# RTDsSheet1.net
KiCad netlist of a schematic drawn in Altium Designer
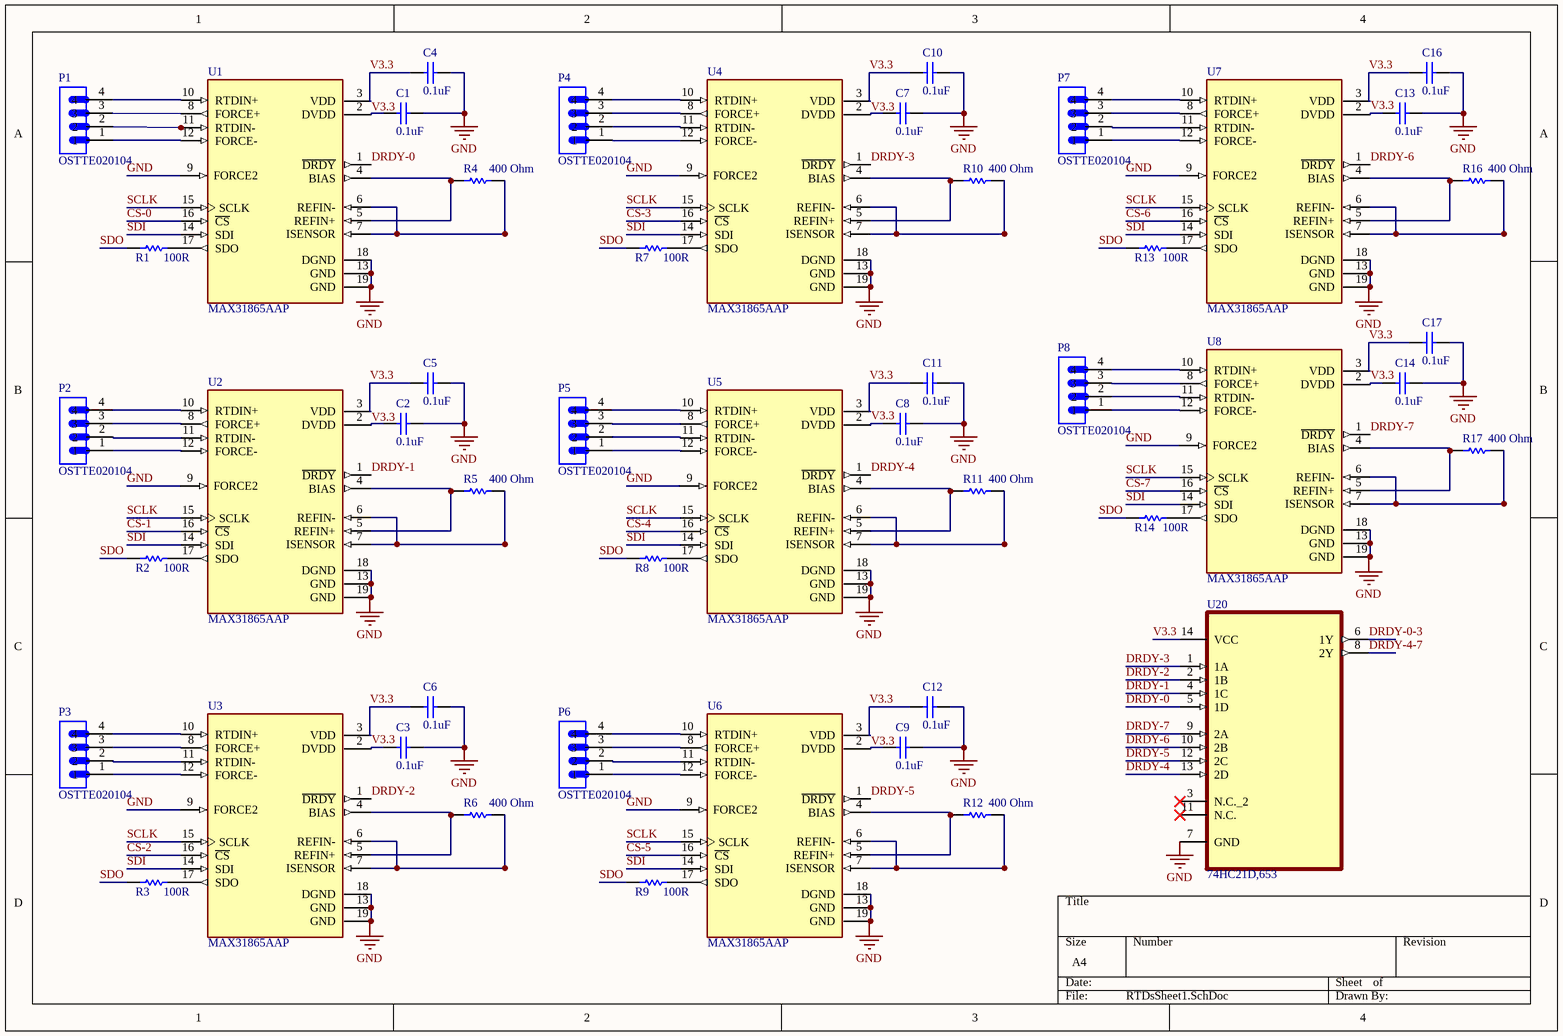
[diagram p0: RTDsSheet1.SchDoc]

(export (version "E")
  (design (tool "Eeschema 10.0.6"))
  (components
    (comp (ref "C1")
      (value "0.1uF")
      (footprint "1608[0603]")
      (description "Capacitor (Semiconductor SIM Model)")
      (fields (field (name "PUBLISHER") "Altium Limited"))
      (libsource (lib "Miscellaneous Devices") (part "Cap Semi"))
    )
    (comp (ref "C2")
      (value "0.1uF")
      (footprint "1608[0603]")
      (description "Capacitor (Semiconductor SIM Model)")
      (fields (field (name "PUBLISHER") "Altium Limited"))
      (libsource (lib "Miscellaneous Devices") (part "Cap Semi"))
    )
    (comp (ref "C3")
      (value "0.1uF")
      (footprint "1608[0603]")
      (description "Capacitor (Semiconductor SIM Model)")
      (fields (field (name "PUBLISHER") "Altium Limited"))
      (libsource (lib "Miscellaneous Devices") (part "Cap Semi"))
    )
    (comp (ref "C4")
      (value "0.1uF")
      (footprint "1608[0603]")
      (description "Capacitor (Semiconductor SIM Model)")
      (fields (field (name "PUBLISHER") "Altium Limited"))
      (libsource (lib "Miscellaneous Devices") (part "Cap Semi"))
    )
    (comp (ref "C5")
      (value "0.1uF")
      (footprint "1608[0603]")
      (description "Capacitor (Semiconductor SIM Model)")
      (fields (field (name "PUBLISHER") "Altium Limited"))
      (libsource (lib "Miscellaneous Devices") (part "Cap Semi"))
    )
    (comp (ref "C6")
      (value "0.1uF")
      (footprint "1608[0603]")
      (description "Capacitor (Semiconductor SIM Model)")
      (fields (field (name "PUBLISHER") "Altium Limited"))
      (libsource (lib "Miscellaneous Devices") (part "Cap Semi"))
    )
    (comp (ref "C7")
      (value "0.1uF")
      (footprint "1608[0603]")
      (description "Capacitor (Semiconductor SIM Model)")
      (fields (field (name "PUBLISHER") "Altium Limited"))
      (libsource (lib "Miscellaneous Devices") (part "Cap Semi"))
    )
    (comp (ref "C8")
      (value "0.1uF")
      (footprint "1608[0603]")
      (description "Capacitor (Semiconductor SIM Model)")
      (fields (field (name "PUBLISHER") "Altium Limited"))
      (libsource (lib "Miscellaneous Devices") (part "Cap Semi"))
    )
    (comp (ref "C9")
      (value "0.1uF")
      (footprint "1608[0603]")
      (description "Capacitor (Semiconductor SIM Model)")
      (fields (field (name "PUBLISHER") "Altium Limited"))
      (libsource (lib "Miscellaneous Devices") (part "Cap Semi"))
    )
    (comp (ref "C10")
      (value "0.1uF")
      (footprint "1608[0603]")
      (description "Capacitor (Semiconductor SIM Model)")
      (fields (field (name "PUBLISHER") "Altium Limited"))
      (libsource (lib "Miscellaneous Devices") (part "Cap Semi"))
    )
    (comp (ref "C11")
      (value "0.1uF")
      (footprint "1608[0603]")
      (description "Capacitor (Semiconductor SIM Model)")
      (fields (field (name "PUBLISHER") "Altium Limited"))
      (libsource (lib "Miscellaneous Devices") (part "Cap Semi"))
    )
    (comp (ref "C12")
      (value "0.1uF")
      (footprint "1608[0603]")
      (description "Capacitor (Semiconductor SIM Model)")
      (fields (field (name "PUBLISHER") "Altium Limited"))
      (libsource (lib "Miscellaneous Devices") (part "Cap Semi"))
    )
    (comp (ref "C13")
      (value "0.1uF")
      (footprint "1608[0603]")
      (description "Capacitor (Semiconductor SIM Model)")
      (fields (field (name "PUBLISHER") "Altium Limited"))
      (libsource (lib "Miscellaneous Devices") (part "Cap Semi"))
    )
    (comp (ref "C14")
      (value "0.1uF")
      (footprint "1608[0603]")
      (description "Capacitor (Semiconductor SIM Model)")
      (fields (field (name "PUBLISHER") "Altium Limited"))
      (libsource (lib "Miscellaneous Devices") (part "Cap Semi"))
    )
    (comp (ref "C16")
      (value "0.1uF")
      (footprint "1608[0603]")
      (description "Capacitor (Semiconductor SIM Model)")
      (fields (field (name "PUBLISHER") "Altium Limited"))
      (libsource (lib "Miscellaneous Devices") (part "Cap Semi"))
    )
    (comp (ref "C17")
      (value "0.1uF")
      (footprint "1608[0603]")
      (description "Capacitor (Semiconductor SIM Model)")
      (fields (field (name "PUBLISHER") "Altium Limited"))
      (libsource (lib "Miscellaneous Devices") (part "Cap Semi"))
    )
    (comp (ref "P1")
      (value "OSTTE020104")
      (footprint "3-641209-4:TE_3-641209-4")
      (description "Terminal Block 3.5mm 2pos Pcb")
      (fields (field (name "MF") "{'manufacturer': u'On Shore'}"))
      (libsource (lib "OSTTE040104") (part "OSTTE020104"))
    )
    (comp (ref "P2")
      (value "OSTTE020104")
      (footprint "3-641209-4:TE_3-641209-4")
      (description "Terminal Block 3.5mm 2pos Pcb")
      (fields (field (name "MF") "{'manufacturer': u'On Shore'}"))
      (libsource (lib "OSTTE040104") (part "OSTTE020104"))
    )
    (comp (ref "P3")
      (value "OSTTE020104")
      (footprint "3-641209-4:TE_3-641209-4")
      (description "Terminal Block 3.5mm 2pos Pcb")
      (fields (field (name "MF") "{'manufacturer': u'On Shore'}"))
      (libsource (lib "OSTTE040104") (part "OSTTE020104"))
    )
    (comp (ref "P4")
      (value "OSTTE020104")
      (footprint "3-641209-4:TE_3-641209-4")
      (description "Terminal Block 3.5mm 2pos Pcb")
      (fields (field (name "MF") "{'manufacturer': u'On Shore'}"))
      (libsource (lib "OSTTE040104") (part "OSTTE020104"))
    )
    (comp (ref "P5")
      (value "OSTTE020104")
      (footprint "3-641209-4:TE_3-641209-4")
      (description "Terminal Block 3.5mm 2pos Pcb")
      (fields (field (name "MF") "{'manufacturer': u'On Shore'}"))
      (libsource (lib "OSTTE040104") (part "OSTTE020104"))
    )
    (comp (ref "P6")
      (value "OSTTE020104")
      (footprint "3-641209-4:TE_3-641209-4")
      (description "Terminal Block 3.5mm 2pos Pcb")
      (fields (field (name "MF") "{'manufacturer': u'On Shore'}"))
      (libsource (lib "OSTTE040104") (part "OSTTE020104"))
    )
    (comp (ref "P7")
      (value "OSTTE020104")
      (footprint "3-641209-4:TE_3-641209-4")
      (description "Terminal Block 3.5mm 2pos Pcb")
      (fields (field (name "MF") "{'manufacturer': u'On Shore'}"))
      (libsource (lib "OSTTE040104") (part "OSTTE020104"))
    )
    (comp (ref "P8")
      (value "OSTTE020104")
      (footprint "3-641209-4:TE_3-641209-4")
      (description "Terminal Block 3.5mm 2pos Pcb")
      (fields (field (name "MF") "{'manufacturer': u'On Shore'}"))
      (libsource (lib "OSTTE040104") (part "OSTTE020104"))
    )
    (comp (ref "R1")
      (value "100R")
      (footprint "1608[0603]")
      (description "Semiconductor Resistor")
      (fields (field (name "PUBLISHER") "Altium Limited"))
      (libsource (lib "Miscellaneous Devices") (part "Res Semi"))
    )
    (comp (ref "R2")
      (value "100R")
      (footprint "1608[0603]")
      (description "Semiconductor Resistor")
      (fields (field (name "PUBLISHER") "Altium Limited"))
      (libsource (lib "Miscellaneous Devices") (part "Res Semi"))
    )
    (comp (ref "R3")
      (value "100R")
      (footprint "1608[0603]")
      (description "Semiconductor Resistor")
      (fields (field (name "PUBLISHER") "Altium Limited"))
      (libsource (lib "Miscellaneous Devices") (part "Res Semi"))
    )
    (comp (ref "R4")
      (value "400 Ohm")
      (footprint "6-0805_M")
      (description "Semiconductor Resistor")
      (fields (field (name "PUBLISHER") "Altium Limited"))
      (libsource (lib "Miscellaneous Devices") (part "Res Semi"))
    )
    (comp (ref "R5")
      (value "400 Ohm")
      (footprint "6-0805_M")
      (description "Semiconductor Resistor")
      (fields (field (name "PUBLISHER") "Altium Limited"))
      (libsource (lib "Miscellaneous Devices") (part "Res Semi"))
    )
    (comp (ref "R6")
      (value "400 Ohm")
      (footprint "6-0805_M")
      (description "Semiconductor Resistor")
      (fields (field (name "PUBLISHER") "Altium Limited"))
      (libsource (lib "Miscellaneous Devices") (part "Res Semi"))
    )
    (comp (ref "R7")
      (value "100R")
      (footprint "1608[0603]")
      (description "Semiconductor Resistor")
      (fields (field (name "PUBLISHER") "Altium Limited"))
      (libsource (lib "Miscellaneous Devices") (part "Res Semi"))
    )
    (comp (ref "R8")
      (value "100R")
      (footprint "1608[0603]")
      (description "Semiconductor Resistor")
      (fields (field (name "PUBLISHER") "Altium Limited"))
      (libsource (lib "Miscellaneous Devices") (part "Res Semi"))
    )
    (comp (ref "R9")
      (value "100R")
      (footprint "1608[0603]")
      (description "Semiconductor Resistor")
      (fields (field (name "PUBLISHER") "Altium Limited"))
      (libsource (lib "Miscellaneous Devices") (part "Res Semi"))
    )
    (comp (ref "R10")
      (value "400 Ohm")
      (footprint "6-0805_M")
      (description "Semiconductor Resistor")
      (fields (field (name "PUBLISHER") "Altium Limited"))
      (libsource (lib "Miscellaneous Devices") (part "Res Semi"))
    )
    (comp (ref "R11")
      (value "400 Ohm")
      (footprint "6-0805_M")
      (description "Semiconductor Resistor")
      (fields (field (name "PUBLISHER") "Altium Limited"))
      (libsource (lib "Miscellaneous Devices") (part "Res Semi"))
    )
    (comp (ref "R12")
      (value "400 Ohm")
      (footprint "6-0805_M")
      (description "Semiconductor Resistor")
      (fields (field (name "PUBLISHER") "Altium Limited"))
      (libsource (lib "Miscellaneous Devices") (part "Res Semi"))
    )
    (comp (ref "R13")
      (value "100R")
      (footprint "1608[0603]")
      (description "Semiconductor Resistor")
      (fields (field (name "PUBLISHER") "Altium Limited"))
      (libsource (lib "Miscellaneous Devices") (part "Res Semi"))
    )
    (comp (ref "R14")
      (value "100R")
      (footprint "1608[0603]")
      (description "Semiconductor Resistor")
      (fields (field (name "PUBLISHER") "Altium Limited"))
      (libsource (lib "Miscellaneous Devices") (part "Res Semi"))
    )
    (comp (ref "R16")
      (value "400 Ohm")
      (footprint "6-0805_M")
      (description "Semiconductor Resistor")
      (fields (field (name "PUBLISHER") "Altium Limited"))
      (libsource (lib "Miscellaneous Devices") (part "Res Semi"))
    )
    (comp (ref "R17")
      (value "400 Ohm")
      (footprint "6-0805_M")
      (description "Semiconductor Resistor")
      (fields (field (name "PUBLISHER") "Altium Limited"))
      (libsource (lib "Miscellaneous Devices") (part "Res Semi"))
    )
    (comp (ref "U1")
      (value "MAX31865AAP")
      (footprint "MAX31865AAP+:SOP65P777X199-20N")
      (description "Rtd To Digital Converter In Ssop Tr")
      (fields (field (name "MF") "{'manufacturer': u'Maxim Integrated'}"))
      (libsource (lib "MAX31865AAP+") (part "MAX31865AAP"))
    )
    (comp (ref "U2")
      (value "MAX31865AAP")
      (footprint "MAX31865AAP+:SOP65P777X199-20N")
      (description "Rtd To Digital Converter In Ssop Tr")
      (fields (field (name "MF") "{'manufacturer': u'Maxim Integrated'}"))
      (libsource (lib "MAX31865AAP+") (part "MAX31865AAP"))
    )
    (comp (ref "U3")
      (value "MAX31865AAP")
      (footprint "MAX31865AAP+:SOP65P777X199-20N")
      (description "Rtd To Digital Converter In Ssop Tr")
      (fields (field (name "MF") "{'manufacturer': u'Maxim Integrated'}"))
      (libsource (lib "MAX31865AAP+") (part "MAX31865AAP"))
    )
    (comp (ref "U4")
      (value "MAX31865AAP")
      (footprint "MAX31865AAP+:SOP65P777X199-20N")
      (description "Rtd To Digital Converter In Ssop Tr")
      (fields (field (name "MF") "{'manufacturer': u'Maxim Integrated'}"))
      (libsource (lib "MAX31865AAP+") (part "MAX31865AAP"))
    )
    (comp (ref "U5")
      (value "MAX31865AAP")
      (footprint "MAX31865AAP+:SOP65P777X199-20N")
      (description "Rtd To Digital Converter In Ssop Tr")
      (fields (field (name "MF") "{'manufacturer': u'Maxim Integrated'}"))
      (libsource (lib "MAX31865AAP+") (part "MAX31865AAP"))
    )
    (comp (ref "U6")
      (value "MAX31865AAP")
      (footprint "MAX31865AAP+:SOP65P777X199-20N")
      (description "Rtd To Digital Converter In Ssop Tr")
      (fields (field (name "MF") "{'manufacturer': u'Maxim Integrated'}"))
      (libsource (lib "MAX31865AAP+") (part "MAX31865AAP"))
    )
    (comp (ref "U7")
      (value "MAX31865AAP")
      (footprint "MAX31865AAP+:SOP65P777X199-20N")
      (description "Rtd To Digital Converter In Ssop Tr")
      (fields (field (name "MF") "{'manufacturer': u'Maxim Integrated'}"))
      (libsource (lib "MAX31865AAP+") (part "MAX31865AAP"))
    )
    (comp (ref "U8")
      (value "MAX31865AAP")
      (footprint "MAX31865AAP+:SOP65P777X199-20N")
      (description "Rtd To Digital Converter In Ssop Tr")
      (fields (field (name "MF") "{'manufacturer': u'Maxim Integrated'}"))
      (libsource (lib "MAX31865AAP+") (part "MAX31865AAP"))
    )
    (comp (ref "U20")
      (value "74HC21D,653")
      (footprint "74HC21D,653:SOIC127P600X175-14N")
      (description "Dual 4-input AND gate")
      (fields (field (name "MF") "{'manufacturer': u'Nexperia USA'}"))
      (libsource (lib "*") (part "74HC21D,653"))
    )
  )
  (nets
    (net (code "1") (name "/CS-0") (class "Default")
      (node (ref "U1") (pin "16") (pinfunction "~{CS}_16") (pintype "input"))
    )
    (net (code "2") (name "/CS-1") (class "Default")
      (node (ref "U2") (pin "16") (pinfunction "~{CS}_16") (pintype "input"))
    )
    (net (code "3") (name "/CS-2") (class "Default")
      (node (ref "U3") (pin "16") (pinfunction "~{CS}_16") (pintype "input"))
    )
    (net (code "4") (name "/CS-3") (class "Default")
      (node (ref "U4") (pin "16") (pinfunction "~{CS}_16") (pintype "input"))
    )
    (net (code "5") (name "/CS-4") (class "Default")
      (node (ref "U5") (pin "16") (pinfunction "~{CS}_16") (pintype "input"))
    )
    (net (code "6") (name "/CS-5") (class "Default")
      (node (ref "U6") (pin "16") (pinfunction "~{CS}_16") (pintype "input"))
    )
    (net (code "7") (name "/CS-6") (class "Default")
      (node (ref "U7") (pin "16") (pinfunction "~{CS}_16") (pintype "input"))
    )
    (net (code "8") (name "/CS-7") (class "Default")
      (node (ref "U8") (pin "16") (pinfunction "~{CS}_16") (pintype "input"))
    )
    (net (code "9") (name "/DRDY-0") (class "Default")
      (node (ref "U1") (pin "1") (pinfunction "~{DRDY}_1") (pintype "output"))
      (node (ref "U20") (pin "5") (pinfunction "1D_5") (pintype "input"))
    )
    (net (code "10") (name "/DRDY-0-3") (class "Default")
      (node (ref "U20") (pin "6") (pinfunction "1Y_6") (pintype "output"))
    )
    (net (code "11") (name "/DRDY-1") (class "Default")
      (node (ref "U2") (pin "1") (pinfunction "~{DRDY}_1") (pintype "output"))
      (node (ref "U20") (pin "4") (pinfunction "1C_4") (pintype "input"))
    )
    (net (code "12") (name "/DRDY-2") (class "Default")
      (node (ref "U20") (pin "2") (pinfunction "1B_2") (pintype "input"))
      (node (ref "U3") (pin "1") (pinfunction "~{DRDY}_1") (pintype "output"))
    )
    (net (code "13") (name "/DRDY-3") (class "Default")
      (node (ref "U20") (pin "1") (pinfunction "1A_1") (pintype "input"))
      (node (ref "U4") (pin "1") (pinfunction "~{DRDY}_1") (pintype "output"))
    )
    (net (code "14") (name "/DRDY-4") (class "Default")
      (node (ref "U20") (pin "13") (pinfunction "2D_13") (pintype "input"))
      (node (ref "U5") (pin "1") (pinfunction "~{DRDY}_1") (pintype "output"))
    )
    (net (code "15") (name "/DRDY-4-7") (class "Default")
      (node (ref "U20") (pin "8") (pinfunction "2Y_8") (pintype "output"))
    )
    (net (code "16") (name "/DRDY-5") (class "Default")
      (node (ref "U20") (pin "12") (pinfunction "2C_12") (pintype "input"))
      (node (ref "U6") (pin "1") (pinfunction "~{DRDY}_1") (pintype "output"))
    )
    (net (code "17") (name "/DRDY-6") (class "Default")
      (node (ref "U20") (pin "10") (pinfunction "2B_10") (pintype "input"))
      (node (ref "U7") (pin "1") (pinfunction "~{DRDY}_1") (pintype "output"))
    )
    (net (code "18") (name "/DRDY-7") (class "Default")
      (node (ref "U20") (pin "9") (pinfunction "2A_9") (pintype "input"))
      (node (ref "U8") (pin "1") (pinfunction "~{DRDY}_1") (pintype "output"))
    )
    (net (code "19") (name "/SCLK") (class "Default")
      (node (ref "U1") (pin "15") (pinfunction "SCLK_15") (pintype "input"))
      (node (ref "U2") (pin "15") (pinfunction "SCLK_15") (pintype "input"))
      (node (ref "U3") (pin "15") (pinfunction "SCLK_15") (pintype "input"))
      (node (ref "U4") (pin "15") (pinfunction "SCLK_15") (pintype "input"))
      (node (ref "U5") (pin "15") (pinfunction "SCLK_15") (pintype "input"))
      (node (ref "U6") (pin "15") (pinfunction "SCLK_15") (pintype "input"))
      (node (ref "U7") (pin "15") (pinfunction "SCLK_15") (pintype "input"))
      (node (ref "U8") (pin "15") (pinfunction "SCLK_15") (pintype "input"))
    )
    (net (code "20") (name "/SDI") (class "Default")
      (node (ref "U1") (pin "14") (pinfunction "SDI_14") (pintype "input"))
      (node (ref "U2") (pin "14") (pinfunction "SDI_14") (pintype "input"))
      (node (ref "U3") (pin "14") (pinfunction "SDI_14") (pintype "input"))
      (node (ref "U4") (pin "14") (pinfunction "SDI_14") (pintype "input"))
      (node (ref "U5") (pin "14") (pinfunction "SDI_14") (pintype "input"))
      (node (ref "U6") (pin "14") (pinfunction "SDI_14") (pintype "input"))
      (node (ref "U7") (pin "14") (pinfunction "SDI_14") (pintype "input"))
      (node (ref "U8") (pin "14") (pinfunction "SDI_14") (pintype "input"))
    )
    (net (code "21") (name "/SDO") (class "Default")
      (node (ref "R1") (pin "2") (pinfunction "2_2") (pintype "passive"))
      (node (ref "R13") (pin "2") (pinfunction "2_2") (pintype "passive"))
      (node (ref "R14") (pin "2") (pinfunction "2_2") (pintype "passive"))
      (node (ref "R2") (pin "2") (pinfunction "2_2") (pintype "passive"))
      (node (ref "R3") (pin "2") (pinfunction "2_2") (pintype "passive"))
      (node (ref "R7") (pin "2") (pinfunction "2_2") (pintype "passive"))
      (node (ref "R8") (pin "2") (pinfunction "2_2") (pintype "passive"))
      (node (ref "R9") (pin "2") (pinfunction "2_2") (pintype "passive"))
    )
    (net (code "22") (name "/V3.3") (class "Default")
      (node (ref "C1") (pin "2") (pinfunction "2_2") (pintype "passive"))
      (node (ref "C10") (pin "2") (pinfunction "2_2") (pintype "passive"))
      (node (ref "C11") (pin "2") (pinfunction "2_2") (pintype "passive"))
      (node (ref "C12") (pin "2") (pinfunction "2_2") (pintype "passive"))
      (node (ref "C13") (pin "2") (pinfunction "2_2") (pintype "passive"))
      (node (ref "C14") (pin "2") (pinfunction "2_2") (pintype "passive"))
      (node (ref "C16") (pin "2") (pinfunction "2_2") (pintype "passive"))
      (node (ref "C17") (pin "2") (pinfunction "2_2") (pintype "passive"))
      (node (ref "C2") (pin "2") (pinfunction "2_2") (pintype "passive"))
      (node (ref "C3") (pin "2") (pinfunction "2_2") (pintype "passive"))
      (node (ref "C4") (pin "2") (pinfunction "2_2") (pintype "passive"))
      (node (ref "C5") (pin "2") (pinfunction "2_2") (pintype "passive"))
      (node (ref "C6") (pin "2") (pinfunction "2_2") (pintype "passive"))
      (node (ref "C7") (pin "2") (pinfunction "2_2") (pintype "passive"))
      (node (ref "C8") (pin "2") (pinfunction "2_2") (pintype "passive"))
      (node (ref "C9") (pin "2") (pinfunction "2_2") (pintype "passive"))
      (node (ref "U1") (pin "2") (pinfunction "DVDD_2") (pintype "power_in"))
      (node (ref "U1") (pin "3") (pinfunction "VDD_3") (pintype "power_in"))
      (node (ref "U2") (pin "2") (pinfunction "DVDD_2") (pintype "power_in"))
      (node (ref "U2") (pin "3") (pinfunction "VDD_3") (pintype "power_in"))
      (node (ref "U20") (pin "14") (pinfunction "VCC_14") (pintype "power_in"))
      (node (ref "U3") (pin "2") (pinfunction "DVDD_2") (pintype "power_in"))
      (node (ref "U3") (pin "3") (pinfunction "VDD_3") (pintype "power_in"))
      (node (ref "U4") (pin "2") (pinfunction "DVDD_2") (pintype "power_in"))
      (node (ref "U4") (pin "3") (pinfunction "VDD_3") (pintype "power_in"))
      (node (ref "U5") (pin "2") (pinfunction "DVDD_2") (pintype "power_in"))
      (node (ref "U5") (pin "3") (pinfunction "VDD_3") (pintype "power_in"))
      (node (ref "U6") (pin "2") (pinfunction "DVDD_2") (pintype "power_in"))
      (node (ref "U6") (pin "3") (pinfunction "VDD_3") (pintype "power_in"))
      (node (ref "U7") (pin "2") (pinfunction "DVDD_2") (pintype "power_in"))
      (node (ref "U7") (pin "3") (pinfunction "VDD_3") (pintype "power_in"))
      (node (ref "U8") (pin "2") (pinfunction "DVDD_2") (pintype "power_in"))
      (node (ref "U8") (pin "3") (pinfunction "VDD_3") (pintype "power_in"))
    )
    (net (code "23") (name "GND") (class "Default")
      (node (ref "C1") (pin "1") (pinfunction "1_1") (pintype "passive"))
      (node (ref "C10") (pin "1") (pinfunction "1_1") (pintype "passive"))
      (node (ref "C11") (pin "1") (pinfunction "1_1") (pintype "passive"))
      (node (ref "C12") (pin "1") (pinfunction "1_1") (pintype "passive"))
      (node (ref "C13") (pin "1") (pinfunction "1_1") (pintype "passive"))
      (node (ref "C14") (pin "1") (pinfunction "1_1") (pintype "passive"))
      (node (ref "C16") (pin "1") (pinfunction "1_1") (pintype "passive"))
      (node (ref "C17") (pin "1") (pinfunction "1_1") (pintype "passive"))
      (node (ref "C2") (pin "1") (pinfunction "1_1") (pintype "passive"))
      (node (ref "C3") (pin "1") (pinfunction "1_1") (pintype "passive"))
      (node (ref "C4") (pin "1") (pinfunction "1_1") (pintype "passive"))
      (node (ref "C5") (pin "1") (pinfunction "1_1") (pintype "passive"))
      (node (ref "C6") (pin "1") (pinfunction "1_1") (pintype "passive"))
      (node (ref "C7") (pin "1") (pinfunction "1_1") (pintype "passive"))
      (node (ref "C8") (pin "1") (pinfunction "1_1") (pintype "passive"))
      (node (ref "C9") (pin "1") (pinfunction "1_1") (pintype "passive"))
      (node (ref "U1") (pin "13") (pinfunction "GND_13") (pintype "power_in"))
      (node (ref "U1") (pin "18") (pinfunction "DGND_18") (pintype "power_in"))
      (node (ref "U1") (pin "19") (pinfunction "GND_19") (pintype "power_in"))
      (node (ref "U1") (pin "9") (pinfunction "FORCE2_9") (pintype "input"))
      (node (ref "U2") (pin "13") (pinfunction "GND_13") (pintype "power_in"))
      (node (ref "U2") (pin "18") (pinfunction "DGND_18") (pintype "power_in"))
      (node (ref "U2") (pin "19") (pinfunction "GND_19") (pintype "power_in"))
      (node (ref "U2") (pin "9") (pinfunction "FORCE2_9") (pintype "input"))
      (node (ref "U20") (pin "7") (pinfunction "GND_7") (pintype "passive"))
      (node (ref "U3") (pin "13") (pinfunction "GND_13") (pintype "power_in"))
      (node (ref "U3") (pin "18") (pinfunction "DGND_18") (pintype "power_in"))
      (node (ref "U3") (pin "19") (pinfunction "GND_19") (pintype "power_in"))
      (node (ref "U3") (pin "9") (pinfunction "FORCE2_9") (pintype "input"))
      (node (ref "U4") (pin "13") (pinfunction "GND_13") (pintype "power_in"))
      (node (ref "U4") (pin "18") (pinfunction "DGND_18") (pintype "power_in"))
      (node (ref "U4") (pin "19") (pinfunction "GND_19") (pintype "power_in"))
      (node (ref "U4") (pin "9") (pinfunction "FORCE2_9") (pintype "input"))
      (node (ref "U5") (pin "13") (pinfunction "GND_13") (pintype "power_in"))
      (node (ref "U5") (pin "18") (pinfunction "DGND_18") (pintype "power_in"))
      (node (ref "U5") (pin "19") (pinfunction "GND_19") (pintype "power_in"))
      (node (ref "U5") (pin "9") (pinfunction "FORCE2_9") (pintype "input"))
      (node (ref "U6") (pin "13") (pinfunction "GND_13") (pintype "power_in"))
      (node (ref "U6") (pin "18") (pinfunction "DGND_18") (pintype "power_in"))
      (node (ref "U6") (pin "19") (pinfunction "GND_19") (pintype "power_in"))
      (node (ref "U6") (pin "9") (pinfunction "FORCE2_9") (pintype "input"))
      (node (ref "U7") (pin "13") (pinfunction "GND_13") (pintype "power_in"))
      (node (ref "U7") (pin "18") (pinfunction "DGND_18") (pintype "power_in"))
      (node (ref "U7") (pin "19") (pinfunction "GND_19") (pintype "power_in"))
      (node (ref "U7") (pin "9") (pinfunction "FORCE2_9") (pintype "input"))
      (node (ref "U8") (pin "13") (pinfunction "GND_13") (pintype "power_in"))
      (node (ref "U8") (pin "18") (pinfunction "DGND_18") (pintype "power_in"))
      (node (ref "U8") (pin "19") (pinfunction "GND_19") (pintype "power_in"))
      (node (ref "U8") (pin "9") (pinfunction "FORCE2_9") (pintype "input"))
    )
    (net (code "24") (name "Net-(U1-BIAS)") (class "Default")
      (node (ref "R4") (pin "2") (pinfunction "2_2") (pintype "passive"))
      (node (ref "U1") (pin "4") (pinfunction "BIAS_4") (pintype "output"))
      (node (ref "U1") (pin "5") (pinfunction "REFIN+_5") (pintype "input"))
    )
    (net (code "25") (name "Net-(U1-FORCE+)") (class "Default")
      (node (ref "P1") (pin "3") (pinfunction "3_3") (pintype "passive"))
      (node (ref "U1") (pin "8") (pinfunction "FORCE+_8") (pintype "output"))
    )
    (net (code "26") (name "Net-(U1-FORCE-)") (class "Default")
      (node (ref "P1") (pin "1") (pinfunction "1_1") (pintype "passive"))
      (node (ref "U1") (pin "12") (pinfunction "FORCE-_12") (pintype "input"))
    )
    (net (code "27") (name "Net-(U1-ISENSOR)") (class "Default")
      (node (ref "R4") (pin "1") (pinfunction "1_1") (pintype "passive"))
      (node (ref "U1") (pin "6") (pinfunction "REFIN-_6") (pintype "input"))
      (node (ref "U1") (pin "7") (pinfunction "ISENSOR_7") (pintype "input"))
    )
    (net (code "28") (name "Net-(U1-RTDIN+)") (class "Default")
      (node (ref "P1") (pin "4") (pinfunction "4_4") (pintype "passive"))
      (node (ref "U1") (pin "10") (pinfunction "RTDIN+_10") (pintype "input"))
    )
    (net (code "29") (name "Net-(U1-RTDIN-)") (class "Default")
      (node (ref "P1") (pin "2") (pinfunction "2_2") (pintype "passive"))
      (node (ref "U1") (pin "11") (pinfunction "RTDIN-_11") (pintype "input"))
    )
    (net (code "30") (name "Net-(U1-SDO)") (class "Default")
      (node (ref "R1") (pin "1") (pinfunction "1_1") (pintype "passive"))
      (node (ref "U1") (pin "17") (pinfunction "SDO_17") (pintype "output"))
    )
    (net (code "31") (name "Net-(U2-BIAS)") (class "Default")
      (node (ref "R5") (pin "2") (pinfunction "2_2") (pintype "passive"))
      (node (ref "U2") (pin "4") (pinfunction "BIAS_4") (pintype "output"))
      (node (ref "U2") (pin "5") (pinfunction "REFIN+_5") (pintype "input"))
    )
    (net (code "32") (name "Net-(U2-FORCE+)") (class "Default")
      (node (ref "P2") (pin "3") (pinfunction "3_3") (pintype "passive"))
      (node (ref "U2") (pin "8") (pinfunction "FORCE+_8") (pintype "output"))
    )
    (net (code "33") (name "Net-(U2-FORCE-)") (class "Default")
      (node (ref "P2") (pin "1") (pinfunction "1_1") (pintype "passive"))
      (node (ref "U2") (pin "12") (pinfunction "FORCE-_12") (pintype "input"))
    )
    (net (code "34") (name "Net-(U2-ISENSOR)") (class "Default")
      (node (ref "R5") (pin "1") (pinfunction "1_1") (pintype "passive"))
      (node (ref "U2") (pin "6") (pinfunction "REFIN-_6") (pintype "input"))
      (node (ref "U2") (pin "7") (pinfunction "ISENSOR_7") (pintype "input"))
    )
    (net (code "35") (name "Net-(U2-RTDIN+)") (class "Default")
      (node (ref "P2") (pin "4") (pinfunction "4_4") (pintype "passive"))
      (node (ref "U2") (pin "10") (pinfunction "RTDIN+_10") (pintype "input"))
    )
    (net (code "36") (name "Net-(U2-RTDIN-)") (class "Default")
      (node (ref "P2") (pin "2") (pinfunction "2_2") (pintype "passive"))
      (node (ref "U2") (pin "11") (pinfunction "RTDIN-_11") (pintype "input"))
    )
    (net (code "37") (name "Net-(U2-SDO)") (class "Default")
      (node (ref "R2") (pin "1") (pinfunction "1_1") (pintype "passive"))
      (node (ref "U2") (pin "17") (pinfunction "SDO_17") (pintype "output"))
    )
    (net (code "38") (name "Net-(U3-BIAS)") (class "Default")
      (node (ref "R6") (pin "2") (pinfunction "2_2") (pintype "passive"))
      (node (ref "U3") (pin "4") (pinfunction "BIAS_4") (pintype "output"))
      (node (ref "U3") (pin "5") (pinfunction "REFIN+_5") (pintype "input"))
    )
    (net (code "39") (name "Net-(U3-FORCE+)") (class "Default")
      (node (ref "P3") (pin "3") (pinfunction "3_3") (pintype "passive"))
      (node (ref "U3") (pin "8") (pinfunction "FORCE+_8") (pintype "output"))
    )
    (net (code "40") (name "Net-(U3-FORCE-)") (class "Default")
      (node (ref "P3") (pin "1") (pinfunction "1_1") (pintype "passive"))
      (node (ref "U3") (pin "12") (pinfunction "FORCE-_12") (pintype "input"))
    )
    (net (code "41") (name "Net-(U3-ISENSOR)") (class "Default")
      (node (ref "R6") (pin "1") (pinfunction "1_1") (pintype "passive"))
      (node (ref "U3") (pin "6") (pinfunction "REFIN-_6") (pintype "input"))
      (node (ref "U3") (pin "7") (pinfunction "ISENSOR_7") (pintype "input"))
    )
    (net (code "42") (name "Net-(U3-RTDIN+)") (class "Default")
      (node (ref "P3") (pin "4") (pinfunction "4_4") (pintype "passive"))
      (node (ref "U3") (pin "10") (pinfunction "RTDIN+_10") (pintype "input"))
    )
    (net (code "43") (name "Net-(U3-RTDIN-)") (class "Default")
      (node (ref "P3") (pin "2") (pinfunction "2_2") (pintype "passive"))
      (node (ref "U3") (pin "11") (pinfunction "RTDIN-_11") (pintype "input"))
    )
    (net (code "44") (name "Net-(U3-SDO)") (class "Default")
      (node (ref "R3") (pin "1") (pinfunction "1_1") (pintype "passive"))
      (node (ref "U3") (pin "17") (pinfunction "SDO_17") (pintype "output"))
    )
    (net (code "45") (name "Net-(U4-BIAS)") (class "Default")
      (node (ref "R10") (pin "2") (pinfunction "2_2") (pintype "passive"))
      (node (ref "U4") (pin "4") (pinfunction "BIAS_4") (pintype "output"))
      (node (ref "U4") (pin "5") (pinfunction "REFIN+_5") (pintype "input"))
    )
    (net (code "46") (name "Net-(U4-FORCE+)") (class "Default")
      (node (ref "P4") (pin "3") (pinfunction "3_3") (pintype "passive"))
      (node (ref "U4") (pin "8") (pinfunction "FORCE+_8") (pintype "output"))
    )
    (net (code "47") (name "Net-(U4-FORCE-)") (class "Default")
      (node (ref "P4") (pin "1") (pinfunction "1_1") (pintype "passive"))
      (node (ref "U4") (pin "12") (pinfunction "FORCE-_12") (pintype "input"))
    )
    (net (code "48") (name "Net-(U4-ISENSOR)") (class "Default")
      (node (ref "R10") (pin "1") (pinfunction "1_1") (pintype "passive"))
      (node (ref "U4") (pin "6") (pinfunction "REFIN-_6") (pintype "input"))
      (node (ref "U4") (pin "7") (pinfunction "ISENSOR_7") (pintype "input"))
    )
    (net (code "49") (name "Net-(U4-RTDIN+)") (class "Default")
      (node (ref "P4") (pin "4") (pinfunction "4_4") (pintype "passive"))
      (node (ref "U4") (pin "10") (pinfunction "RTDIN+_10") (pintype "input"))
    )
    (net (code "50") (name "Net-(U4-RTDIN-)") (class "Default")
      (node (ref "P4") (pin "2") (pinfunction "2_2") (pintype "passive"))
      (node (ref "U4") (pin "11") (pinfunction "RTDIN-_11") (pintype "input"))
    )
    (net (code "51") (name "Net-(U4-SDO)") (class "Default")
      (node (ref "R7") (pin "1") (pinfunction "1_1") (pintype "passive"))
      (node (ref "U4") (pin "17") (pinfunction "SDO_17") (pintype "output"))
    )
    (net (code "52") (name "Net-(U5-BIAS)") (class "Default")
      (node (ref "R11") (pin "2") (pinfunction "2_2") (pintype "passive"))
      (node (ref "U5") (pin "4") (pinfunction "BIAS_4") (pintype "output"))
      (node (ref "U5") (pin "5") (pinfunction "REFIN+_5") (pintype "input"))
    )
    (net (code "53") (name "Net-(U5-FORCE+)") (class "Default")
      (node (ref "P5") (pin "3") (pinfunction "3_3") (pintype "passive"))
      (node (ref "U5") (pin "8") (pinfunction "FORCE+_8") (pintype "output"))
    )
    (net (code "54") (name "Net-(U5-FORCE-)") (class "Default")
      (node (ref "P5") (pin "1") (pinfunction "1_1") (pintype "passive"))
      (node (ref "U5") (pin "12") (pinfunction "FORCE-_12") (pintype "input"))
    )
    (net (code "55") (name "Net-(U5-ISENSOR)") (class "Default")
      (node (ref "R11") (pin "1") (pinfunction "1_1") (pintype "passive"))
      (node (ref "U5") (pin "6") (pinfunction "REFIN-_6") (pintype "input"))
      (node (ref "U5") (pin "7") (pinfunction "ISENSOR_7") (pintype "input"))
    )
    (net (code "56") (name "Net-(U5-RTDIN+)") (class "Default")
      (node (ref "P5") (pin "4") (pinfunction "4_4") (pintype "passive"))
      (node (ref "U5") (pin "10") (pinfunction "RTDIN+_10") (pintype "input"))
    )
    (net (code "57") (name "Net-(U5-RTDIN-)") (class "Default")
      (node (ref "P5") (pin "2") (pinfunction "2_2") (pintype "passive"))
      (node (ref "U5") (pin "11") (pinfunction "RTDIN-_11") (pintype "input"))
    )
    (net (code "58") (name "Net-(U5-SDO)") (class "Default")
      (node (ref "R8") (pin "1") (pinfunction "1_1") (pintype "passive"))
      (node (ref "U5") (pin "17") (pinfunction "SDO_17") (pintype "output"))
    )
    (net (code "59") (name "Net-(U6-BIAS)") (class "Default")
      (node (ref "R12") (pin "2") (pinfunction "2_2") (pintype "passive"))
      (node (ref "U6") (pin "4") (pinfunction "BIAS_4") (pintype "output"))
      (node (ref "U6") (pin "5") (pinfunction "REFIN+_5") (pintype "input"))
    )
    (net (code "60") (name "Net-(U6-FORCE+)") (class "Default")
      (node (ref "P6") (pin "3") (pinfunction "3_3") (pintype "passive"))
      (node (ref "U6") (pin "8") (pinfunction "FORCE+_8") (pintype "output"))
    )
    (net (code "61") (name "Net-(U6-FORCE-)") (class "Default")
      (node (ref "P6") (pin "1") (pinfunction "1_1") (pintype "passive"))
      (node (ref "U6") (pin "12") (pinfunction "FORCE-_12") (pintype "input"))
    )
    (net (code "62") (name "Net-(U6-ISENSOR)") (class "Default")
      (node (ref "R12") (pin "1") (pinfunction "1_1") (pintype "passive"))
      (node (ref "U6") (pin "6") (pinfunction "REFIN-_6") (pintype "input"))
      (node (ref "U6") (pin "7") (pinfunction "ISENSOR_7") (pintype "input"))
    )
    (net (code "63") (name "Net-(U6-RTDIN+)") (class "Default")
      (node (ref "P6") (pin "4") (pinfunction "4_4") (pintype "passive"))
      (node (ref "U6") (pin "10") (pinfunction "RTDIN+_10") (pintype "input"))
    )
    (net (code "64") (name "Net-(U6-RTDIN-)") (class "Default")
      (node (ref "P6") (pin "2") (pinfunction "2_2") (pintype "passive"))
      (node (ref "U6") (pin "11") (pinfunction "RTDIN-_11") (pintype "input"))
    )
    (net (code "65") (name "Net-(U6-SDO)") (class "Default")
      (node (ref "R9") (pin "1") (pinfunction "1_1") (pintype "passive"))
      (node (ref "U6") (pin "17") (pinfunction "SDO_17") (pintype "output"))
    )
    (net (code "66") (name "Net-(U7-BIAS)") (class "Default")
      (node (ref "R16") (pin "2") (pinfunction "2_2") (pintype "passive"))
      (node (ref "U7") (pin "4") (pinfunction "BIAS_4") (pintype "output"))
      (node (ref "U7") (pin "5") (pinfunction "REFIN+_5") (pintype "input"))
    )
    (net (code "67") (name "Net-(U7-FORCE+)") (class "Default")
      (node (ref "P7") (pin "3") (pinfunction "3_3") (pintype "passive"))
      (node (ref "U7") (pin "8") (pinfunction "FORCE+_8") (pintype "output"))
    )
    (net (code "68") (name "Net-(U7-FORCE-)") (class "Default")
      (node (ref "P7") (pin "1") (pinfunction "1_1") (pintype "passive"))
      (node (ref "U7") (pin "12") (pinfunction "FORCE-_12") (pintype "input"))
    )
    (net (code "69") (name "Net-(U7-ISENSOR)") (class "Default")
      (node (ref "R16") (pin "1") (pinfunction "1_1") (pintype "passive"))
      (node (ref "U7") (pin "6") (pinfunction "REFIN-_6") (pintype "input"))
      (node (ref "U7") (pin "7") (pinfunction "ISENSOR_7") (pintype "input"))
    )
    (net (code "70") (name "Net-(U7-RTDIN+)") (class "Default")
      (node (ref "P7") (pin "4") (pinfunction "4_4") (pintype "passive"))
      (node (ref "U7") (pin "10") (pinfunction "RTDIN+_10") (pintype "input"))
    )
    (net (code "71") (name "Net-(U7-RTDIN-)") (class "Default")
      (node (ref "P7") (pin "2") (pinfunction "2_2") (pintype "passive"))
      (node (ref "U7") (pin "11") (pinfunction "RTDIN-_11") (pintype "input"))
    )
    (net (code "72") (name "Net-(U7-SDO)") (class "Default")
      (node (ref "R13") (pin "1") (pinfunction "1_1") (pintype "passive"))
      (node (ref "U7") (pin "17") (pinfunction "SDO_17") (pintype "output"))
    )
    (net (code "73") (name "Net-(U8-BIAS)") (class "Default")
      (node (ref "R17") (pin "2") (pinfunction "2_2") (pintype "passive"))
      (node (ref "U8") (pin "4") (pinfunction "BIAS_4") (pintype "output"))
      (node (ref "U8") (pin "5") (pinfunction "REFIN+_5") (pintype "input"))
    )
    (net (code "74") (name "Net-(U8-FORCE+)") (class "Default")
      (node (ref "P8") (pin "3") (pinfunction "3_3") (pintype "passive"))
      (node (ref "U8") (pin "8") (pinfunction "FORCE+_8") (pintype "output"))
    )
    (net (code "75") (name "Net-(U8-FORCE-)") (class "Default")
      (node (ref "P8") (pin "1") (pinfunction "1_1") (pintype "passive"))
      (node (ref "U8") (pin "12") (pinfunction "FORCE-_12") (pintype "input"))
    )
    (net (code "76") (name "Net-(U8-ISENSOR)") (class "Default")
      (node (ref "R17") (pin "1") (pinfunction "1_1") (pintype "passive"))
      (node (ref "U8") (pin "6") (pinfunction "REFIN-_6") (pintype "input"))
      (node (ref "U8") (pin "7") (pinfunction "ISENSOR_7") (pintype "input"))
    )
    (net (code "77") (name "Net-(U8-RTDIN+)") (class "Default")
      (node (ref "P8") (pin "4") (pinfunction "4_4") (pintype "passive"))
      (node (ref "U8") (pin "10") (pinfunction "RTDIN+_10") (pintype "input"))
    )
    (net (code "78") (name "Net-(U8-RTDIN-)") (class "Default")
      (node (ref "P8") (pin "2") (pinfunction "2_2") (pintype "passive"))
      (node (ref "U8") (pin "11") (pinfunction "RTDIN-_11") (pintype "input"))
    )
    (net (code "79") (name "Net-(U8-SDO)") (class "Default")
      (node (ref "R14") (pin "1") (pinfunction "1_1") (pintype "passive"))
      (node (ref "U8") (pin "17") (pinfunction "SDO_17") (pintype "output"))
    )
    (net (code "80") (name "unconnected-(U20-N.C.-Pad11)") (class "Default")
      (node (ref "U20") (pin "11") (pinfunction "N.C._11") (pintype "passive+no_connect"))
    )
    (net (code "81") (name "unconnected-(U20-N.C._2-Pad3)") (class "Default")
      (node (ref "U20") (pin "3") (pinfunction "N.C._2_3") (pintype "passive+no_connect"))
    )
  )
)
